# Coolrunner_JTAG_Power.net
KiCad netlist of a schematic drawn in Altium Designer
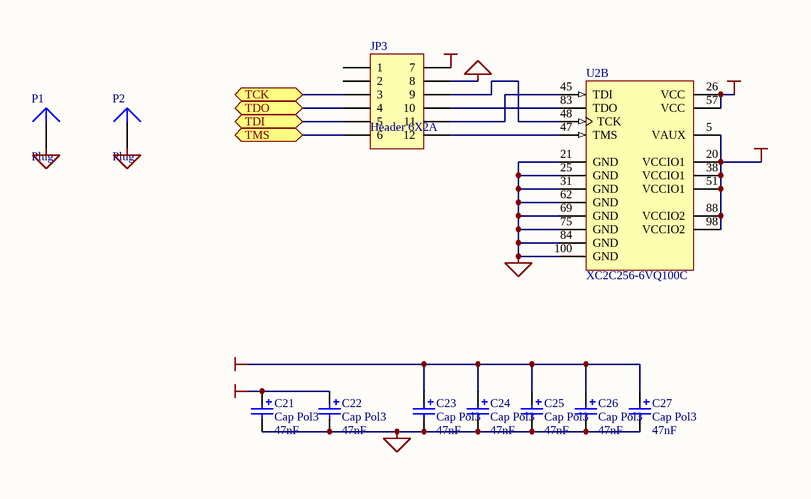
[diagram p0: Coolrunner_JTAG_Power.SchDoc]

(export (version "E")
  (design (tool "Eeschema 10.0.6"))
  (components
    (comp (ref "C21")
      (value "Cap Pol3")
      (footprint "CAP 10")
      (description "Polarized Capacitor (Surface Mount)")
      (fields (field (name "ALTIUM_VALUE") "47nF") (field (name "PUBLISHER") "Altium Limited"))
      (libsource (lib "Miscellaneous Devices") (part "Cap Pol3"))
    )
    (comp (ref "C22")
      (value "Cap Pol3")
      (footprint "CAP 10")
      (description "Polarized Capacitor (Surface Mount)")
      (fields (field (name "ALTIUM_VALUE") "47nF") (field (name "PUBLISHER") "Altium Limited"))
      (libsource (lib "Miscellaneous Devices") (part "Cap Pol3"))
    )
    (comp (ref "C23")
      (value "Cap Pol3")
      (footprint "CAP 10")
      (description "Polarized Capacitor (Surface Mount)")
      (fields (field (name "ALTIUM_VALUE") "47nF") (field (name "PUBLISHER") "Altium Limited"))
      (libsource (lib "Miscellaneous Devices") (part "Cap Pol3"))
    )
    (comp (ref "C24")
      (value "Cap Pol3")
      (footprint "CAP 10")
      (description "Polarized Capacitor (Surface Mount)")
      (fields (field (name "ALTIUM_VALUE") "47nF") (field (name "PUBLISHER") "Altium Limited"))
      (libsource (lib "Miscellaneous Devices") (part "Cap Pol3"))
    )
    (comp (ref "C25")
      (value "Cap Pol3")
      (footprint "CAP 10")
      (description "Polarized Capacitor (Surface Mount)")
      (fields (field (name "ALTIUM_VALUE") "47nF") (field (name "PUBLISHER") "Altium Limited"))
      (libsource (lib "Miscellaneous Devices") (part "Cap Pol3"))
    )
    (comp (ref "C26")
      (value "Cap Pol3")
      (footprint "CAP 10")
      (description "Polarized Capacitor (Surface Mount)")
      (fields (field (name "ALTIUM_VALUE") "47nF") (field (name "PUBLISHER") "Altium Limited"))
      (libsource (lib "Miscellaneous Devices") (part "Cap Pol3"))
    )
    (comp (ref "C27")
      (value "Cap Pol3")
      (footprint "CAP 10")
      (description "Polarized Capacitor (Surface Mount)")
      (fields (field (name "ALTIUM_VALUE") "47nF") (field (name "PUBLISHER") "Altium Limited"))
      (libsource (lib "Miscellaneous Devices") (part "Cap Pol3"))
    )
    (comp (ref "JP3")
      (value "Header 6X2A")
      (footprint "HDR2X6_CEN")
      (description "Header, 6-Pin, Dual row")
      (fields (field (name "PUBLISHER") "Altium Limited"))
      (libsource (lib "Miscellaneous Connectors") (part "Header 6X2A"))
    )
    (comp (ref "P1")
      (value "Plug")
      (footprint "PIN1")
      (fields (field (name "PUBLISHER") "Altium Limited"))
      (libsource (lib "Miscellaneous Connectors") (part "Plug"))
    )
    (comp (ref "P2")
      (value "Plug")
      (footprint "PIN1")
      (fields (field (name "PUBLISHER") "Altium Limited"))
      (libsource (lib "Miscellaneous Connectors") (part "Plug"))
    )
    (comp (ref "U2")
      (value "XC2C256-6VQ100C")
      (footprint "VQ100")
      (description "CoolRunner-II, 1.8V, 256 Macrocell CPLD, 100-Pin VQFP, Commercial Grade")
      (fields (field (name "PUBLISHER") "Altium Limited"))
      (libsource (lib "Xilinx CoolRunner II") (part "XC2C256-6VQ100C"))
    )
  )
  (nets
    (net (code "1") (name "/TCK") (class "Default")
      (node (ref "JP3") (pin "3") (pinfunction "3_3") (pintype "passive"))
    )
    (net (code "2") (name "/TDI") (class "Default")
      (node (ref "JP3") (pin "5") (pinfunction "5_5") (pintype "passive"))
    )
    (net (code "3") (name "/TDO") (class "Default")
      (node (ref "JP3") (pin "4") (pinfunction "4_4") (pintype "passive"))
    )
    (net (code "4") (name "/TMS") (class "Default")
      (node (ref "JP3") (pin "6") (pinfunction "6_6") (pintype "passive"))
    )
    (net (code "5") (name "1.8V") (class "Default")
      (node (ref "C21") (pin "1") (pinfunction "1_1") (pintype "passive"))
      (node (ref "C22") (pin "1") (pinfunction "1_1") (pintype "passive"))
      (node (ref "U2") (pin "26") (pinfunction "VCC_26") (pintype "power_in"))
      (node (ref "U2") (pin "57") (pinfunction "VCC_57") (pintype "power_in"))
    )
    (net (code "6") (name "3.3V") (class "Default")
      (node (ref "C23") (pin "1") (pinfunction "1_1") (pintype "passive"))
      (node (ref "C24") (pin "1") (pinfunction "1_1") (pintype "passive"))
      (node (ref "C25") (pin "1") (pinfunction "1_1") (pintype "passive"))
      (node (ref "C26") (pin "1") (pinfunction "1_1") (pintype "passive"))
      (node (ref "C27") (pin "1") (pinfunction "1_1") (pintype "passive"))
      (node (ref "JP3") (pin "7") (pinfunction "7_7") (pintype "passive"))
      (node (ref "U2") (pin "20") (pinfunction "VCCIO1_20") (pintype "power_in"))
      (node (ref "U2") (pin "38") (pinfunction "VCCIO1_38") (pintype "power_in"))
      (node (ref "U2") (pin "5") (pinfunction "VAUX_5") (pintype "power_in"))
      (node (ref "U2") (pin "51") (pinfunction "VCCIO1_51") (pintype "power_in"))
      (node (ref "U2") (pin "88") (pinfunction "VCCIO2_88") (pintype "power_in"))
      (node (ref "U2") (pin "98") (pinfunction "VCCIO2_98") (pintype "power_in"))
    )
    (net (code "7") (name "GND") (class "Default")
      (node (ref "C21") (pin "2") (pinfunction "2_2") (pintype "passive"))
      (node (ref "C22") (pin "2") (pinfunction "2_2") (pintype "passive"))
      (node (ref "C23") (pin "2") (pinfunction "2_2") (pintype "passive"))
      (node (ref "C24") (pin "2") (pinfunction "2_2") (pintype "passive"))
      (node (ref "C25") (pin "2") (pinfunction "2_2") (pintype "passive"))
      (node (ref "C26") (pin "2") (pinfunction "2_2") (pintype "passive"))
      (node (ref "C27") (pin "2") (pinfunction "2_2") (pintype "passive"))
      (node (ref "JP3") (pin "8") (pinfunction "8_8") (pintype "passive"))
      (node (ref "P1") (pin "1") (pinfunction "1_1") (pintype "passive"))
      (node (ref "P2") (pin "1") (pinfunction "1_1") (pintype "passive"))
      (node (ref "U2") (pin "100") (pinfunction "GND_100") (pintype "power_in"))
      (node (ref "U2") (pin "21") (pinfunction "GND_21") (pintype "power_in"))
      (node (ref "U2") (pin "25") (pinfunction "GND_25") (pintype "power_in"))
      (node (ref "U2") (pin "31") (pinfunction "GND_31") (pintype "power_in"))
      (node (ref "U2") (pin "62") (pinfunction "GND_62") (pintype "power_in"))
      (node (ref "U2") (pin "69") (pinfunction "GND_69") (pintype "power_in"))
      (node (ref "U2") (pin "75") (pinfunction "GND_75") (pintype "power_in"))
      (node (ref "U2") (pin "84") (pinfunction "GND_84") (pintype "power_in"))
    )
    (net (code "8") (name "Net-(U2B-TCK)") (class "Default")
      (node (ref "JP3") (pin "9") (pinfunction "9_9") (pintype "passive"))
      (node (ref "U2") (pin "48") (pinfunction "TCK_48") (pintype "input"))
    )
    (net (code "9") (name "Net-(U2B-TDI)") (class "Default")
      (node (ref "JP3") (pin "11") (pinfunction "11_11") (pintype "passive"))
      (node (ref "U2") (pin "45") (pinfunction "TDI_45") (pintype "input"))
    )
    (net (code "10") (name "Net-(U2B-TDO)") (class "Default")
      (node (ref "JP3") (pin "10") (pinfunction "10_10") (pintype "passive"))
      (node (ref "U2") (pin "83") (pinfunction "TDO_83") (pintype "tri_state"))
    )
    (net (code "11") (name "Net-(U2B-TMS)") (class "Default")
      (node (ref "JP3") (pin "12") (pinfunction "12_12") (pintype "passive"))
      (node (ref "U2") (pin "47") (pinfunction "TMS_47") (pintype "input"))
    )
    (net (code "12") (name "unconnected-(JP3-Pad1)") (class "Default")
      (node (ref "JP3") (pin "1") (pinfunction "1_1") (pintype "passive"))
    )
    (net (code "13") (name "unconnected-(JP3-Pad2)") (class "Default")
      (node (ref "JP3") (pin "2") (pinfunction "2_2") (pintype "passive"))
    )
  )
)
